# item_2223_analog.net
KiCad netlist of a schematic drawn in EAGLE
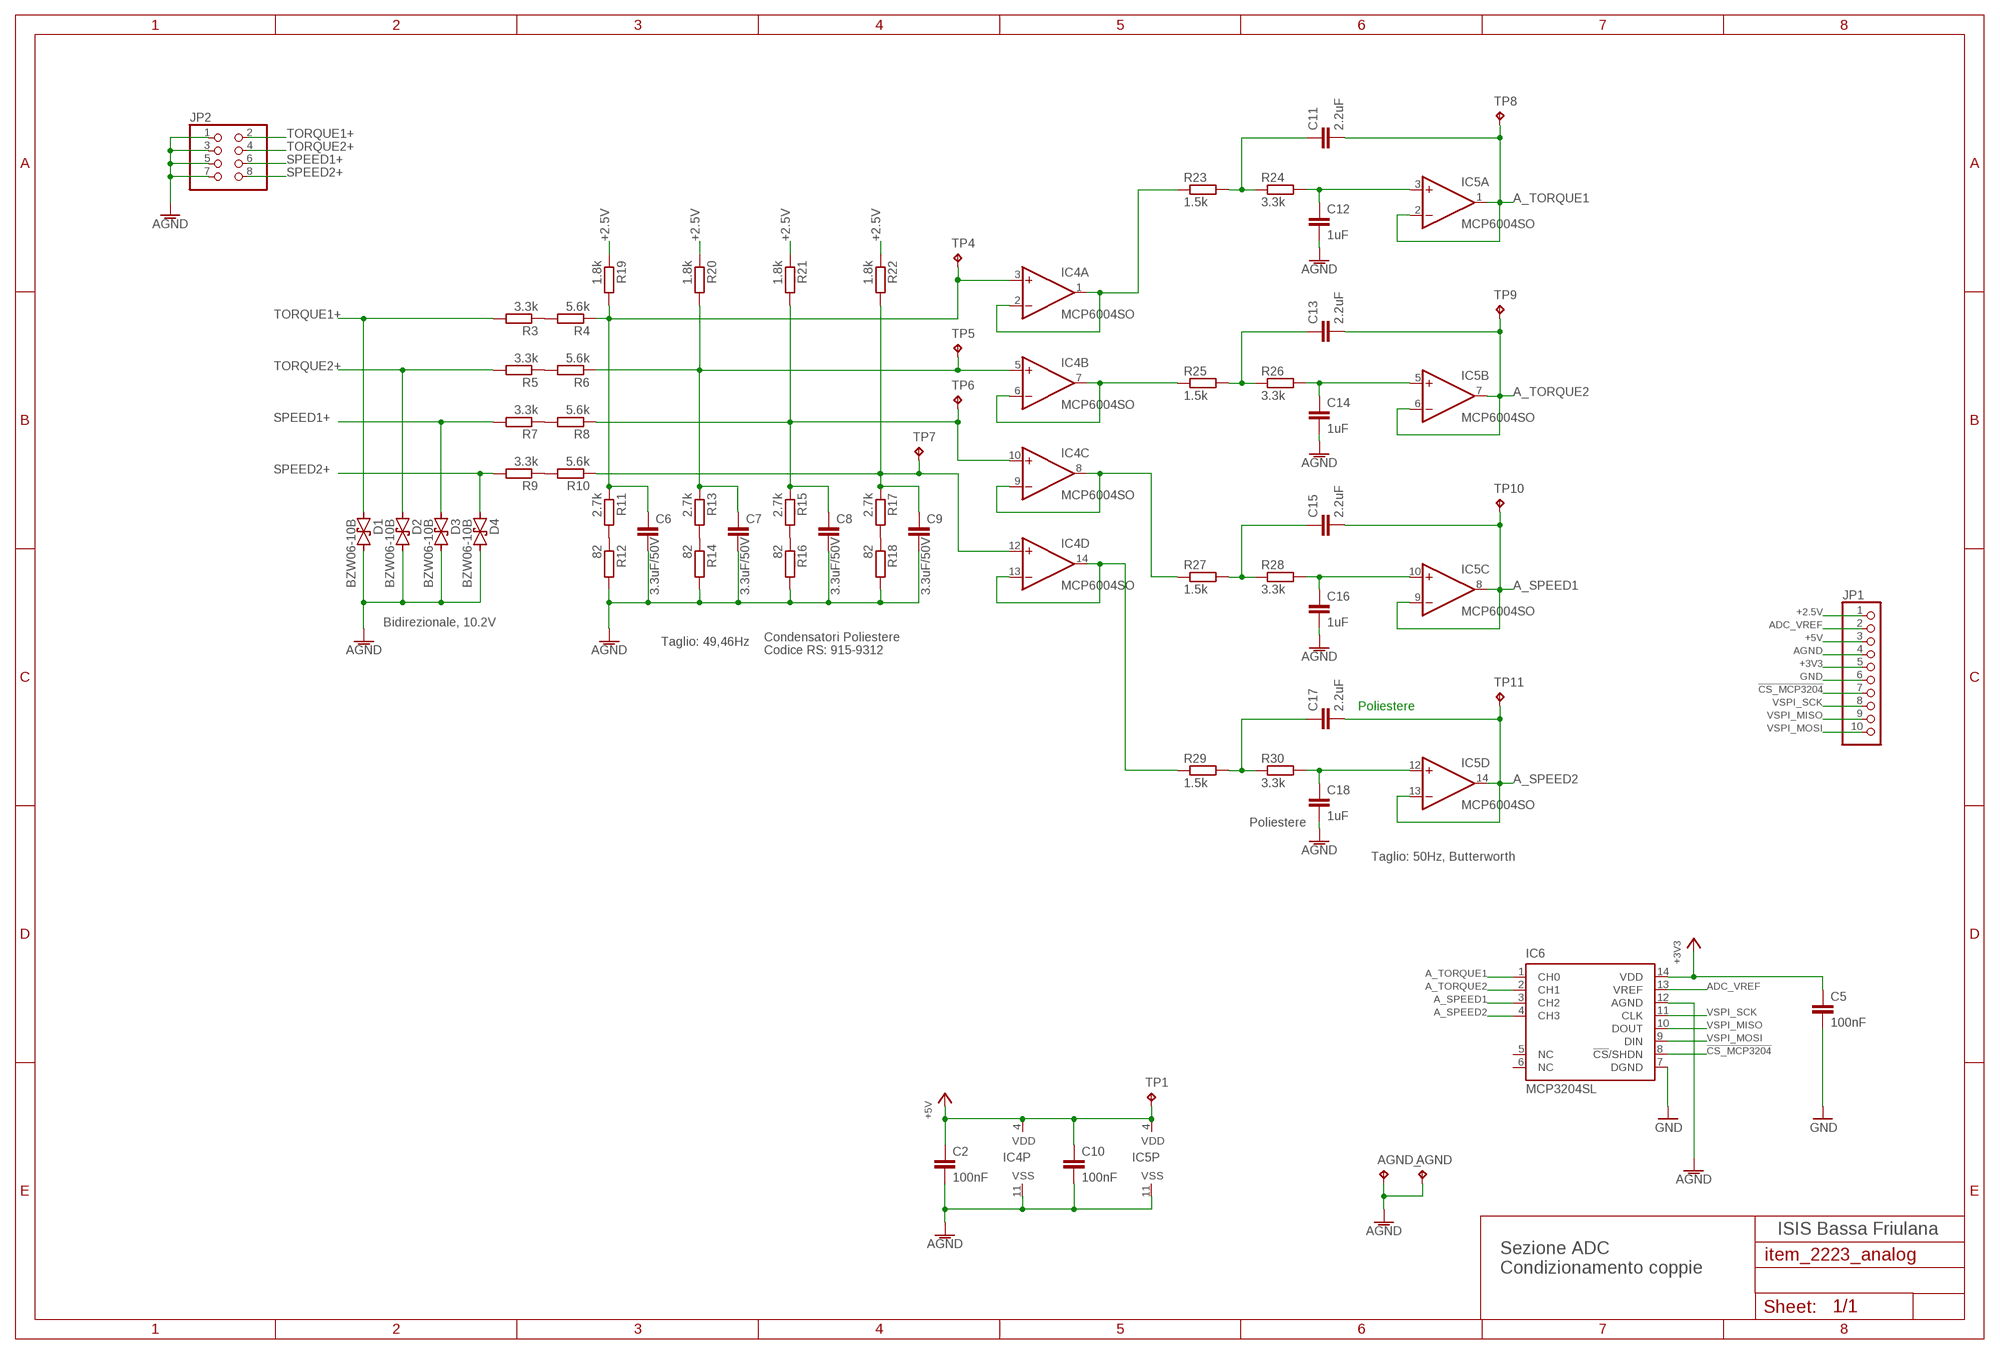
[diagram p0: schematic, sheet 1]

(export (version "E")
  (design (tool "Eeschema 10.0.6"))
  (components
    (comp (ref "AGND")
      (value "TPTP18SQ")
      (footprint "eagle-import:TP18SQ")
      (libsource (lib "eagle-import") (part "TPTP18SQ"))
    )
    (comp (ref "AGND_")
      (value "TPTP18SQ")
      (footprint "eagle-import:TP18SQ")
      (libsource (lib "eagle-import") (part "TPTP18SQ"))
    )
    (comp (ref "C2")
      (value "100nF")
      (footprint "eagle-import:C0805")
      (libsource (lib "eagle-import") (part "C-EUC0805"))
    )
    (comp (ref "C5")
      (value "100nF")
      (footprint "eagle-import:C0805")
      (libsource (lib "eagle-import") (part "C-EUC0805"))
    )
    (comp (ref "C6")
      (value "3.3uF/50V")
      (footprint "eagle-import:C0805")
      (libsource (lib "eagle-import") (part "C-EUC0805"))
    )
    (comp (ref "C7")
      (value "3.3uF/50V")
      (footprint "eagle-import:C0805")
      (libsource (lib "eagle-import") (part "C-EUC0805"))
    )
    (comp (ref "C8")
      (value "3.3uF/50V")
      (footprint "eagle-import:C0805")
      (libsource (lib "eagle-import") (part "C-EUC0805"))
    )
    (comp (ref "C9")
      (value "3.3uF/50V")
      (footprint "eagle-import:C0805")
      (libsource (lib "eagle-import") (part "C-EUC0805"))
    )
    (comp (ref "C10")
      (value "100nF")
      (footprint "eagle-import:C0805")
      (libsource (lib "eagle-import") (part "C-EUC0805"))
    )
    (comp (ref "C11")
      (value "2.2uF")
      (footprint "eagle-import:C0805")
      (libsource (lib "eagle-import") (part "C-EUC0805"))
    )
    (comp (ref "C12")
      (value "1uF")
      (footprint "eagle-import:C0805")
      (libsource (lib "eagle-import") (part "C-EUC0805"))
    )
    (comp (ref "C13")
      (value "2.2uF")
      (footprint "eagle-import:C0805")
      (libsource (lib "eagle-import") (part "C-EUC0805"))
    )
    (comp (ref "C14")
      (value "1uF")
      (footprint "eagle-import:C0805")
      (libsource (lib "eagle-import") (part "C-EUC0805"))
    )
    (comp (ref "C15")
      (value "2.2uF")
      (footprint "eagle-import:C0805")
      (libsource (lib "eagle-import") (part "C-EUC0805"))
    )
    (comp (ref "C16")
      (value "1uF")
      (footprint "eagle-import:C0805")
      (libsource (lib "eagle-import") (part "C-EUC0805"))
    )
    (comp (ref "C17")
      (value "2.2uF")
      (footprint "eagle-import:C0805")
      (libsource (lib "eagle-import") (part "C-EUC0805"))
    )
    (comp (ref "C18")
      (value "1uF")
      (footprint "eagle-import:C0805")
      (libsource (lib "eagle-import") (part "C-EUC0805"))
    )
    (comp (ref "D1")
      (value "BZW06-10B")
      (footprint "eagle-import:F126Z12")
      (libsource (lib "eagle-import") (part "BZW04XXB"))
    )
    (comp (ref "D2")
      (value "BZW06-10B")
      (footprint "eagle-import:F126Z12")
      (libsource (lib "eagle-import") (part "BZW04XXB"))
    )
    (comp (ref "D3")
      (value "BZW06-10B")
      (footprint "eagle-import:F126Z12")
      (libsource (lib "eagle-import") (part "BZW04XXB"))
    )
    (comp (ref "D4")
      (value "BZW06-10B")
      (footprint "eagle-import:F126Z12")
      (libsource (lib "eagle-import") (part "BZW04XXB"))
    )
    (comp (ref "IC4")
      (value "MCP6004SO")
      (footprint "eagle-import:SO14")
      (libsource (lib "eagle-import") (part "MCP6004SO"))
    )
    (comp (ref "IC5")
      (value "MCP6004SO")
      (footprint "eagle-import:SO14")
      (libsource (lib "eagle-import") (part "MCP6004SO"))
    )
    (comp (ref "IC6")
      (value "MCP3204SL")
      (footprint "eagle-import:SO14")
      (libsource (lib "eagle-import") (part "MCP3204SL"))
    )
    (comp (ref "JP1")
      (value "PINHD-1X10")
      (footprint "eagle-import:1X10")
      (libsource (lib "eagle-import") (part "PINHD-1X10"))
    )
    (comp (ref "JP2")
      (value "PINHD-2X4")
      (footprint "eagle-import:2X04")
      (libsource (lib "eagle-import") (part "PINHD-2X4"))
    )
    (comp (ref "R3")
      (value "3.3k")
      (footprint "eagle-import:R0805")
      (libsource (lib "eagle-import") (part "R-EU_R0805"))
    )
    (comp (ref "R4")
      (value "5.6k")
      (footprint "eagle-import:R0805")
      (libsource (lib "eagle-import") (part "R-EU_R0805"))
    )
    (comp (ref "R5")
      (value "3.3k")
      (footprint "eagle-import:R0805")
      (libsource (lib "eagle-import") (part "R-EU_R0805"))
    )
    (comp (ref "R6")
      (value "5.6k")
      (footprint "eagle-import:R0805")
      (libsource (lib "eagle-import") (part "R-EU_R0805"))
    )
    (comp (ref "R7")
      (value "3.3k")
      (footprint "eagle-import:M0805")
      (libsource (lib "eagle-import") (part "R-EU_M0805"))
    )
    (comp (ref "R8")
      (value "5.6k")
      (footprint "eagle-import:R0805")
      (libsource (lib "eagle-import") (part "R-EU_R0805"))
    )
    (comp (ref "R9")
      (value "3.3k")
      (footprint "eagle-import:R0805")
      (libsource (lib "eagle-import") (part "R-EU_R0805"))
    )
    (comp (ref "R10")
      (value "5.6k")
      (footprint "eagle-import:R0805")
      (libsource (lib "eagle-import") (part "R-EU_R0805"))
    )
    (comp (ref "R11")
      (value "2.7k")
      (footprint "eagle-import:R0805")
      (libsource (lib "eagle-import") (part "R-EU_R0805"))
    )
    (comp (ref "R12")
      (value "82")
      (footprint "eagle-import:R0805")
      (libsource (lib "eagle-import") (part "R-EU_R0805"))
    )
    (comp (ref "R13")
      (value "2.7k")
      (footprint "eagle-import:R0805")
      (libsource (lib "eagle-import") (part "R-EU_R0805"))
    )
    (comp (ref "R14")
      (value "82")
      (footprint "eagle-import:R0805")
      (libsource (lib "eagle-import") (part "R-EU_R0805"))
    )
    (comp (ref "R15")
      (value "2.7k")
      (footprint "eagle-import:R0805")
      (libsource (lib "eagle-import") (part "R-EU_R0805"))
    )
    (comp (ref "R16")
      (value "82")
      (footprint "eagle-import:R0805")
      (libsource (lib "eagle-import") (part "R-EU_R0805"))
    )
    (comp (ref "R17")
      (value "2.7k")
      (footprint "eagle-import:R0805")
      (libsource (lib "eagle-import") (part "R-EU_R0805"))
    )
    (comp (ref "R18")
      (value "82")
      (footprint "eagle-import:R0805")
      (libsource (lib "eagle-import") (part "R-EU_R0805"))
    )
    (comp (ref "R19")
      (value "1.8k")
      (footprint "eagle-import:R0805")
      (libsource (lib "eagle-import") (part "R-EU_R0805"))
    )
    (comp (ref "R20")
      (value "1.8k")
      (footprint "eagle-import:R0805")
      (libsource (lib "eagle-import") (part "R-EU_R0805"))
    )
    (comp (ref "R21")
      (value "1.8k")
      (footprint "eagle-import:R0805")
      (libsource (lib "eagle-import") (part "R-EU_R0805"))
    )
    (comp (ref "R22")
      (value "1.8k")
      (footprint "eagle-import:R0805")
      (libsource (lib "eagle-import") (part "R-EU_R0805"))
    )
    (comp (ref "R23")
      (value "1.5k")
      (footprint "eagle-import:R0805")
      (libsource (lib "eagle-import") (part "R-EU_R0805"))
    )
    (comp (ref "R24")
      (value "3.3k")
      (footprint "eagle-import:R0805")
      (libsource (lib "eagle-import") (part "R-EU_R0805"))
    )
    (comp (ref "R25")
      (value "1.5k")
      (footprint "eagle-import:R0805")
      (libsource (lib "eagle-import") (part "R-EU_R0805"))
    )
    (comp (ref "R26")
      (value "3.3k")
      (footprint "eagle-import:R0805")
      (libsource (lib "eagle-import") (part "R-EU_R0805"))
    )
    (comp (ref "R27")
      (value "1.5k")
      (footprint "eagle-import:R0805")
      (libsource (lib "eagle-import") (part "R-EU_R0805"))
    )
    (comp (ref "R28")
      (value "3.3k")
      (footprint "eagle-import:R0805")
      (libsource (lib "eagle-import") (part "R-EU_R0805"))
    )
    (comp (ref "R29")
      (value "1.5k")
      (footprint "eagle-import:R0805")
      (libsource (lib "eagle-import") (part "R-EU_R0805"))
    )
    (comp (ref "R30")
      (value "3.3k")
      (footprint "eagle-import:R0805")
      (libsource (lib "eagle-import") (part "R-EU_R0805"))
    )
    (comp (ref "TP1")
      (value "TPTP16R")
      (footprint "eagle-import:TP16R")
      (libsource (lib "eagle-import") (part "TPTP16R"))
    )
    (comp (ref "TP4")
      (value "TPTP14R")
      (footprint "eagle-import:TP14R")
      (libsource (lib "eagle-import") (part "TPTP14R"))
    )
    (comp (ref "TP5")
      (value "TPTP14R")
      (footprint "eagle-import:TP14R")
      (libsource (lib "eagle-import") (part "TPTP14R"))
    )
    (comp (ref "TP6")
      (value "TPTP14R")
      (footprint "eagle-import:TP14R")
      (libsource (lib "eagle-import") (part "TPTP14R"))
    )
    (comp (ref "TP7")
      (value "TPTP14R")
      (footprint "eagle-import:TP14R")
      (libsource (lib "eagle-import") (part "TPTP14R"))
    )
    (comp (ref "TP8")
      (value "TPTP14R")
      (footprint "eagle-import:TP14R")
      (libsource (lib "eagle-import") (part "TPTP14R"))
    )
    (comp (ref "TP9")
      (value "TPTP14R")
      (footprint "eagle-import:TP14R")
      (libsource (lib "eagle-import") (part "TPTP14R"))
    )
    (comp (ref "TP10")
      (value "TPTP14R")
      (footprint "eagle-import:TP14R")
      (libsource (lib "eagle-import") (part "TPTP14R"))
    )
    (comp (ref "TP11")
      (value "TPTP14R")
      (footprint "eagle-import:TP14R")
      (libsource (lib "eagle-import") (part "TPTP14R"))
    )
  )
  (nets
    (net (code "1") (name "+3V3") (class "Default")
      (node (ref "C5") (pin "1") (pinfunction "1_1") (pintype "passive"))
      (node (ref "IC6") (pin "14") (pinfunction "VDD_14") (pintype "power_in"))
      (node (ref "JP1") (pin "5") (pinfunction "5_5") (pintype "passive"))
    )
    (net (code "2") (name "+5V") (class "Default")
      (node (ref "C10") (pin "1") (pinfunction "1_1") (pintype "passive"))
      (node (ref "C2") (pin "1") (pinfunction "1_1") (pintype "passive"))
      (node (ref "IC4") (pin "4") (pinfunction "VDD_4") (pintype "power_in"))
      (node (ref "IC5") (pin "4") (pinfunction "VDD_4") (pintype "power_in"))
      (node (ref "JP1") (pin "3") (pinfunction "3_3") (pintype "passive"))
      (node (ref "TP1") (pin "TP") (pinfunction "TP_TP") (pintype "input"))
    )
    (net (code "3") (name "/+2.5V") (class "Default")
      (node (ref "JP1") (pin "1") (pinfunction "1_1") (pintype "passive"))
      (node (ref "R19") (pin "1") (pinfunction "1_1") (pintype "passive"))
      (node (ref "R20") (pin "1") (pinfunction "1_1") (pintype "passive"))
      (node (ref "R21") (pin "1") (pinfunction "1_1") (pintype "passive"))
      (node (ref "R22") (pin "1") (pinfunction "1_1") (pintype "passive"))
    )
    (net (code "4") (name "/ADC_VREF") (class "Default")
      (node (ref "IC6") (pin "13") (pinfunction "VREF_13") (pintype "power_in"))
      (node (ref "JP1") (pin "2") (pinfunction "2_2") (pintype "passive"))
    )
    (net (code "5") (name "/A_SPEED1") (class "Default")
      (node (ref "C15") (pin "2") (pinfunction "2_2") (pintype "passive"))
      (node (ref "IC5") (pin "8") (pinfunction "OUT_8") (pintype "output"))
      (node (ref "IC5") (pin "9") (pinfunction "-IN_9") (pintype "input"))
      (node (ref "IC6") (pin "3") (pinfunction "CH2_3") (pintype "input"))
      (node (ref "TP10") (pin "TP") (pinfunction "TP_TP") (pintype "input"))
    )
    (net (code "6") (name "/A_SPEED2") (class "Default")
      (node (ref "C17") (pin "2") (pinfunction "2_2") (pintype "passive"))
      (node (ref "IC5") (pin "13") (pinfunction "-IN_13") (pintype "input"))
      (node (ref "IC5") (pin "14") (pinfunction "OUT_14") (pintype "output"))
      (node (ref "IC6") (pin "4") (pinfunction "CH3_4") (pintype "input"))
      (node (ref "TP11") (pin "TP") (pinfunction "TP_TP") (pintype "input"))
    )
    (net (code "7") (name "/A_TORQUE1") (class "Default")
      (node (ref "C11") (pin "2") (pinfunction "2_2") (pintype "passive"))
      (node (ref "IC5") (pin "1") (pinfunction "OUT_1") (pintype "output"))
      (node (ref "IC5") (pin "2") (pinfunction "-IN_2") (pintype "input"))
      (node (ref "IC6") (pin "1") (pinfunction "CH0_1") (pintype "input"))
      (node (ref "TP8") (pin "TP") (pinfunction "TP_TP") (pintype "input"))
    )
    (net (code "8") (name "/A_TORQUE2") (class "Default")
      (node (ref "C13") (pin "2") (pinfunction "2_2") (pintype "passive"))
      (node (ref "IC5") (pin "6") (pinfunction "-IN_6") (pintype "input"))
      (node (ref "IC5") (pin "7") (pinfunction "OUT_7") (pintype "output"))
      (node (ref "IC6") (pin "2") (pinfunction "CH1_2") (pintype "input"))
      (node (ref "TP9") (pin "TP") (pinfunction "TP_TP") (pintype "input"))
    )
    (net (code "9") (name "/SPEED1+") (class "Default")
      (node (ref "D3") (pin "A") (pinfunction "1_A") (pintype "passive"))
      (node (ref "JP2") (pin "6") (pinfunction "6_6") (pintype "passive"))
      (node (ref "R7") (pin "2") (pinfunction "2_2") (pintype "passive"))
    )
    (net (code "10") (name "/SPEED2+") (class "Default")
      (node (ref "D4") (pin "A") (pinfunction "1_A") (pintype "passive"))
      (node (ref "JP2") (pin "8") (pinfunction "8_8") (pintype "passive"))
      (node (ref "R9") (pin "2") (pinfunction "2_2") (pintype "passive"))
    )
    (net (code "11") (name "/TORQUE1+") (class "Default")
      (node (ref "D1") (pin "A") (pinfunction "1_A") (pintype "passive"))
      (node (ref "JP2") (pin "2") (pinfunction "2_2") (pintype "passive"))
      (node (ref "R3") (pin "2") (pinfunction "2_2") (pintype "passive"))
    )
    (net (code "12") (name "/TORQUE2+") (class "Default")
      (node (ref "D2") (pin "A") (pinfunction "1_A") (pintype "passive"))
      (node (ref "JP2") (pin "4") (pinfunction "4_4") (pintype "passive"))
      (node (ref "R5") (pin "2") (pinfunction "2_2") (pintype "passive"))
    )
    (net (code "13") (name "/VSPI_MISO") (class "Default")
      (node (ref "IC6") (pin "10") (pinfunction "DOUT_10") (pintype "input"))
      (node (ref "JP1") (pin "9") (pinfunction "9_9") (pintype "passive"))
    )
    (net (code "14") (name "/VSPI_MOSI") (class "Default")
      (node (ref "IC6") (pin "9") (pinfunction "DIN_9") (pintype "input"))
      (node (ref "JP1") (pin "10") (pinfunction "10_10") (pintype "passive"))
    )
    (net (code "15") (name "/VSPI_SCK") (class "Default")
      (node (ref "IC6") (pin "11") (pinfunction "CLK_11") (pintype "input"))
      (node (ref "JP1") (pin "8") (pinfunction "8_8") (pintype "passive"))
    )
    (net (code "16") (name "/~{CS_MCP3204}") (class "Default")
      (node (ref "IC6") (pin "8") (pinfunction "~{CS}/SHDN_8") (pintype "input"))
      (node (ref "JP1") (pin "7") (pinfunction "7_7") (pintype "passive"))
    )
    (net (code "17") (name "AGND") (class "Default")
      (node (ref "AGND") (pin "TP") (pinfunction "TP_TP") (pintype "input"))
      (node (ref "AGND_") (pin "TP") (pinfunction "TP_TP") (pintype "input"))
      (node (ref "C10") (pin "2") (pinfunction "2_2") (pintype "passive"))
      (node (ref "C12") (pin "2") (pinfunction "2_2") (pintype "passive"))
      (node (ref "C14") (pin "2") (pinfunction "2_2") (pintype "passive"))
      (node (ref "C16") (pin "2") (pinfunction "2_2") (pintype "passive"))
      (node (ref "C18") (pin "2") (pinfunction "2_2") (pintype "passive"))
      (node (ref "C2") (pin "2") (pinfunction "2_2") (pintype "passive"))
      (node (ref "C6") (pin "2") (pinfunction "2_2") (pintype "passive"))
      (node (ref "C7") (pin "2") (pinfunction "2_2") (pintype "passive"))
      (node (ref "C8") (pin "2") (pinfunction "2_2") (pintype "passive"))
      (node (ref "C9") (pin "2") (pinfunction "2_2") (pintype "passive"))
      (node (ref "D1") (pin "C") (pinfunction "2_C") (pintype "passive"))
      (node (ref "D2") (pin "C") (pinfunction "2_C") (pintype "passive"))
      (node (ref "D3") (pin "C") (pinfunction "2_C") (pintype "passive"))
      (node (ref "D4") (pin "C") (pinfunction "2_C") (pintype "passive"))
      (node (ref "IC4") (pin "11") (pinfunction "VSS_11") (pintype "power_in"))
      (node (ref "IC5") (pin "11") (pinfunction "VSS_11") (pintype "power_in"))
      (node (ref "IC6") (pin "12") (pinfunction "AGND_12") (pintype "power_in"))
      (node (ref "JP1") (pin "4") (pinfunction "4_4") (pintype "passive"))
      (node (ref "JP2") (pin "1") (pinfunction "1_1") (pintype "passive"))
      (node (ref "JP2") (pin "3") (pinfunction "3_3") (pintype "passive"))
      (node (ref "JP2") (pin "5") (pinfunction "5_5") (pintype "passive"))
      (node (ref "JP2") (pin "7") (pinfunction "7_7") (pintype "passive"))
      (node (ref "R12") (pin "2") (pinfunction "2_2") (pintype "passive"))
      (node (ref "R14") (pin "2") (pinfunction "2_2") (pintype "passive"))
      (node (ref "R16") (pin "2") (pinfunction "2_2") (pintype "passive"))
      (node (ref "R18") (pin "2") (pinfunction "2_2") (pintype "passive"))
    )
    (net (code "18") (name "GND") (class "Default")
      (node (ref "C5") (pin "2") (pinfunction "2_2") (pintype "passive"))
      (node (ref "IC6") (pin "7") (pinfunction "DGND_7") (pintype "power_in"))
      (node (ref "JP1") (pin "6") (pinfunction "6_6") (pintype "passive"))
    )
    (net (code "19") (name "Net-(C11-Pad1)") (class "Default")
      (node (ref "C11") (pin "1") (pinfunction "1_1") (pintype "passive"))
      (node (ref "R23") (pin "2") (pinfunction "2_2") (pintype "passive"))
      (node (ref "R24") (pin "1") (pinfunction "1_1") (pintype "passive"))
    )
    (net (code "20") (name "Net-(C13-Pad1)") (class "Default")
      (node (ref "C13") (pin "1") (pinfunction "1_1") (pintype "passive"))
      (node (ref "R25") (pin "2") (pinfunction "2_2") (pintype "passive"))
      (node (ref "R26") (pin "1") (pinfunction "1_1") (pintype "passive"))
    )
    (net (code "21") (name "Net-(C15-Pad1)") (class "Default")
      (node (ref "C15") (pin "1") (pinfunction "1_1") (pintype "passive"))
      (node (ref "R27") (pin "2") (pinfunction "2_2") (pintype "passive"))
      (node (ref "R28") (pin "1") (pinfunction "1_1") (pintype "passive"))
    )
    (net (code "22") (name "Net-(C17-Pad1)") (class "Default")
      (node (ref "C17") (pin "1") (pinfunction "1_1") (pintype "passive"))
      (node (ref "R29") (pin "2") (pinfunction "2_2") (pintype "passive"))
      (node (ref "R30") (pin "1") (pinfunction "1_1") (pintype "passive"))
    )
    (net (code "23") (name "Net-(IC4A-+IN)") (class "Default")
      (node (ref "C6") (pin "1") (pinfunction "1_1") (pintype "passive"))
      (node (ref "IC4") (pin "3") (pinfunction "+IN_3") (pintype "input"))
      (node (ref "R11") (pin "1") (pinfunction "1_1") (pintype "passive"))
      (node (ref "R19") (pin "2") (pinfunction "2_2") (pintype "passive"))
      (node (ref "R4") (pin "1") (pinfunction "1_1") (pintype "passive"))
      (node (ref "TP4") (pin "TP") (pinfunction "TP_TP") (pintype "input"))
    )
    (net (code "24") (name "Net-(IC4A--IN)") (class "Default")
      (node (ref "IC4") (pin "1") (pinfunction "OUT_1") (pintype "output"))
      (node (ref "IC4") (pin "2") (pinfunction "-IN_2") (pintype "input"))
      (node (ref "R23") (pin "1") (pinfunction "1_1") (pintype "passive"))
    )
    (net (code "25") (name "Net-(IC4B-+IN)") (class "Default")
      (node (ref "C7") (pin "1") (pinfunction "1_1") (pintype "passive"))
      (node (ref "IC4") (pin "5") (pinfunction "+IN_5") (pintype "input"))
      (node (ref "R13") (pin "1") (pinfunction "1_1") (pintype "passive"))
      (node (ref "R20") (pin "2") (pinfunction "2_2") (pintype "passive"))
      (node (ref "R6") (pin "1") (pinfunction "1_1") (pintype "passive"))
      (node (ref "TP5") (pin "TP") (pinfunction "TP_TP") (pintype "input"))
    )
    (net (code "26") (name "Net-(IC4B--IN)") (class "Default")
      (node (ref "IC4") (pin "6") (pinfunction "-IN_6") (pintype "input"))
      (node (ref "IC4") (pin "7") (pinfunction "OUT_7") (pintype "output"))
      (node (ref "R25") (pin "1") (pinfunction "1_1") (pintype "passive"))
    )
    (net (code "27") (name "Net-(IC4C-+IN)") (class "Default")
      (node (ref "C8") (pin "1") (pinfunction "1_1") (pintype "passive"))
      (node (ref "IC4") (pin "10") (pinfunction "+IN_10") (pintype "input"))
      (node (ref "R15") (pin "1") (pinfunction "1_1") (pintype "passive"))
      (node (ref "R21") (pin "2") (pinfunction "2_2") (pintype "passive"))
      (node (ref "R8") (pin "1") (pinfunction "1_1") (pintype "passive"))
      (node (ref "TP6") (pin "TP") (pinfunction "TP_TP") (pintype "input"))
    )
    (net (code "28") (name "Net-(IC4C--IN)") (class "Default")
      (node (ref "IC4") (pin "8") (pinfunction "OUT_8") (pintype "output"))
      (node (ref "IC4") (pin "9") (pinfunction "-IN_9") (pintype "input"))
      (node (ref "R27") (pin "1") (pinfunction "1_1") (pintype "passive"))
    )
    (net (code "29") (name "Net-(IC4D-+IN)") (class "Default")
      (node (ref "C9") (pin "1") (pinfunction "1_1") (pintype "passive"))
      (node (ref "IC4") (pin "12") (pinfunction "+IN_12") (pintype "input"))
      (node (ref "R10") (pin "1") (pinfunction "1_1") (pintype "passive"))
      (node (ref "R17") (pin "1") (pinfunction "1_1") (pintype "passive"))
      (node (ref "R22") (pin "2") (pinfunction "2_2") (pintype "passive"))
      (node (ref "TP7") (pin "TP") (pinfunction "TP_TP") (pintype "input"))
    )
    (net (code "30") (name "Net-(IC4D--IN)") (class "Default")
      (node (ref "IC4") (pin "13") (pinfunction "-IN_13") (pintype "input"))
      (node (ref "IC4") (pin "14") (pinfunction "OUT_14") (pintype "output"))
      (node (ref "R29") (pin "1") (pinfunction "1_1") (pintype "passive"))
    )
    (net (code "31") (name "Net-(IC5A-+IN)") (class "Default")
      (node (ref "C12") (pin "1") (pinfunction "1_1") (pintype "passive"))
      (node (ref "IC5") (pin "3") (pinfunction "+IN_3") (pintype "input"))
      (node (ref "R24") (pin "2") (pinfunction "2_2") (pintype "passive"))
    )
    (net (code "32") (name "Net-(IC5B-+IN)") (class "Default")
      (node (ref "C14") (pin "1") (pinfunction "1_1") (pintype "passive"))
      (node (ref "IC5") (pin "5") (pinfunction "+IN_5") (pintype "input"))
      (node (ref "R26") (pin "2") (pinfunction "2_2") (pintype "passive"))
    )
    (net (code "33") (name "Net-(IC5C-+IN)") (class "Default")
      (node (ref "C16") (pin "1") (pinfunction "1_1") (pintype "passive"))
      (node (ref "IC5") (pin "10") (pinfunction "+IN_10") (pintype "input"))
      (node (ref "R28") (pin "2") (pinfunction "2_2") (pintype "passive"))
    )
    (net (code "34") (name "Net-(IC5D-+IN)") (class "Default")
      (node (ref "C18") (pin "1") (pinfunction "1_1") (pintype "passive"))
      (node (ref "IC5") (pin "12") (pinfunction "+IN_12") (pintype "input"))
      (node (ref "R30") (pin "2") (pinfunction "2_2") (pintype "passive"))
    )
    (net (code "35") (name "Net-(R3-Pad1)") (class "Default")
      (node (ref "R3") (pin "1") (pinfunction "1_1") (pintype "passive"))
      (node (ref "R4") (pin "2") (pinfunction "2_2") (pintype "passive"))
    )
    (net (code "36") (name "Net-(R5-Pad1)") (class "Default")
      (node (ref "R5") (pin "1") (pinfunction "1_1") (pintype "passive"))
      (node (ref "R6") (pin "2") (pinfunction "2_2") (pintype "passive"))
    )
    (net (code "37") (name "Net-(R7-Pad1)") (class "Default")
      (node (ref "R7") (pin "1") (pinfunction "1_1") (pintype "passive"))
      (node (ref "R8") (pin "2") (pinfunction "2_2") (pintype "passive"))
    )
    (net (code "38") (name "Net-(R10-Pad2)") (class "Default")
      (node (ref "R10") (pin "2") (pinfunction "2_2") (pintype "passive"))
      (node (ref "R9") (pin "1") (pinfunction "1_1") (pintype "passive"))
    )
    (net (code "39") (name "Net-(R11-Pad2)") (class "Default")
      (node (ref "R11") (pin "2") (pinfunction "2_2") (pintype "passive"))
      (node (ref "R12") (pin "1") (pinfunction "1_1") (pintype "passive"))
    )
    (net (code "40") (name "Net-(R13-Pad2)") (class "Default")
      (node (ref "R13") (pin "2") (pinfunction "2_2") (pintype "passive"))
      (node (ref "R14") (pin "1") (pinfunction "1_1") (pintype "passive"))
    )
    (net (code "41") (name "Net-(R15-Pad2)") (class "Default")
      (node (ref "R15") (pin "2") (pinfunction "2_2") (pintype "passive"))
      (node (ref "R16") (pin "1") (pinfunction "1_1") (pintype "passive"))
    )
    (net (code "42") (name "Net-(R17-Pad2)") (class "Default")
      (node (ref "R17") (pin "2") (pinfunction "2_2") (pintype "passive"))
      (node (ref "R18") (pin "1") (pinfunction "1_1") (pintype "passive"))
    )
    (net (code "43") (name "unconnected-(IC6-NC-Pad5)") (class "Default")
      (node (ref "IC6") (pin "5") (pinfunction "NC_5") (pintype "no_connect"))
    )
    (net (code "44") (name "unconnected-(IC6-NC-Pad6)") (class "Default")
      (node (ref "IC6") (pin "6") (pinfunction "NC_6") (pintype "no_connect"))
    )
  )
)
